# Kilobot_Controller_Hub_FTDI.net
KiCad netlist of a schematic drawn in Altium Designer
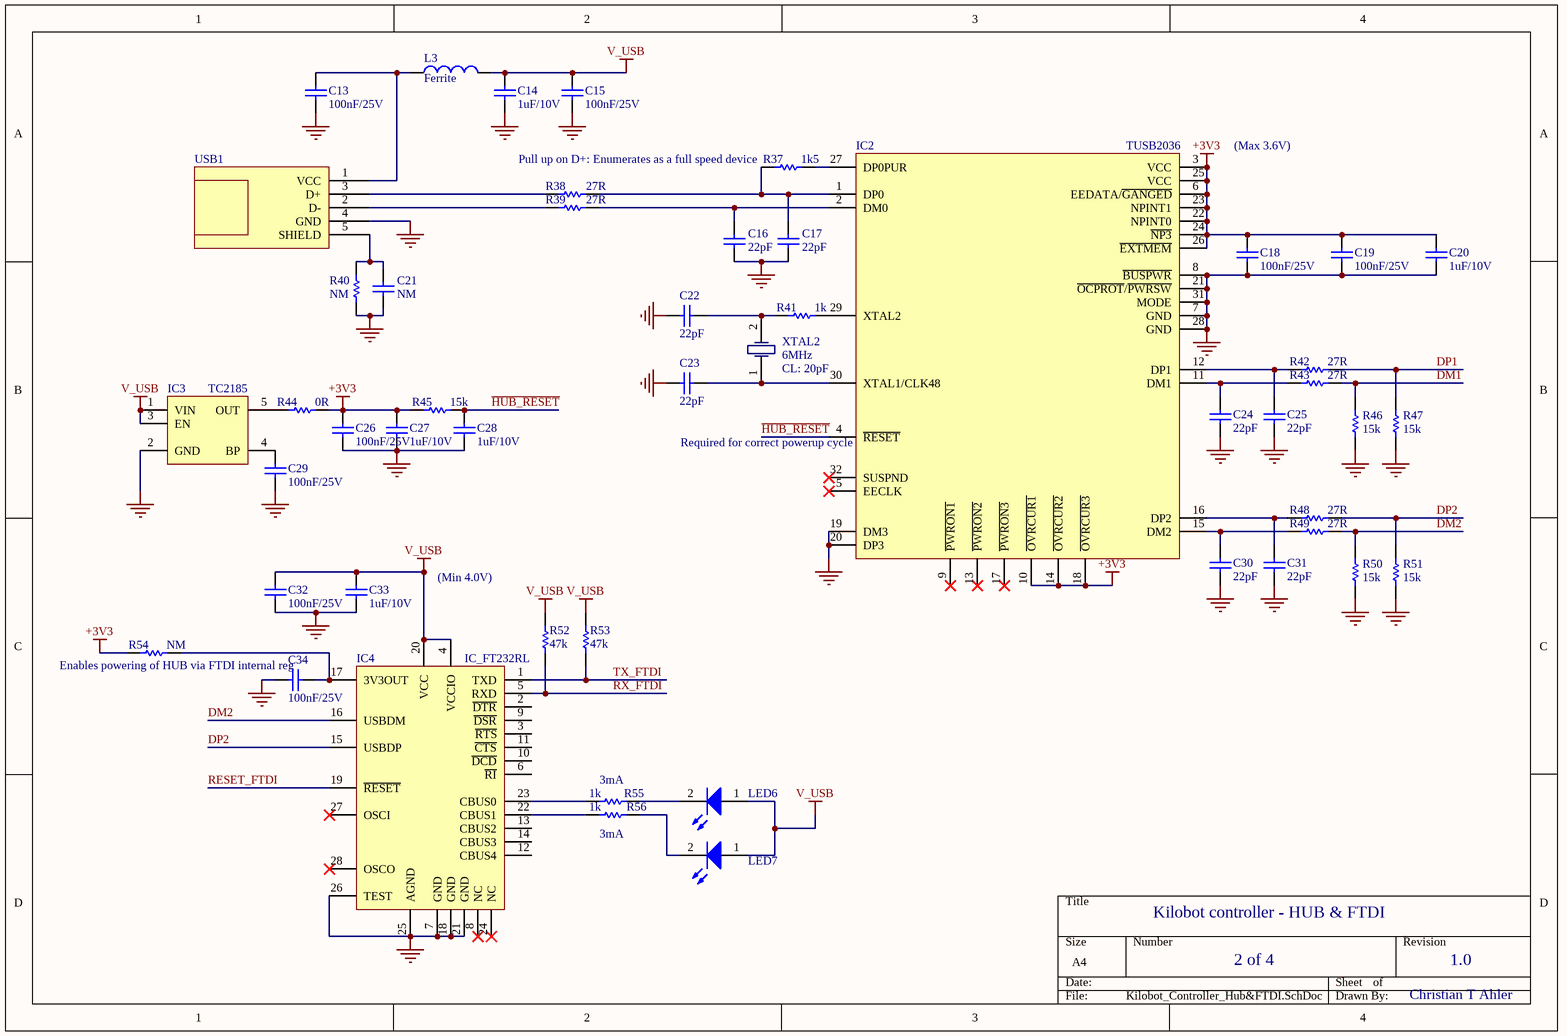
[diagram p0: Kilobot_Controller_Hub&FTDI.SchDoc]

(export (version "E")
  (design (tool "Eeschema 10.0.6"))
  (components
    (comp (ref "C13")
      (value "100nF/25V")
      (footprint "RESC1608L")
      (description "Ceramic Chip Capacitor - Standard")
      (fields (field (name "Comment") "C0603"))
      (libsource (lib "KEMET Chip Capacitor") (part "C0603"))
    )
    (comp (ref "C14")
      (value "1uF/10V")
      (footprint "RESC1608L")
      (description "Ceramic Chip Capacitor - Standard")
      (fields (field (name "Comment") "C0603"))
      (libsource (lib "KEMET Chip Capacitor") (part "C0603"))
    )
    (comp (ref "C15")
      (value "100nF/25V")
      (footprint "RESC1608L")
      (description "Ceramic Chip Capacitor - Standard")
      (fields (field (name "Comment") "C0603"))
      (libsource (lib "KEMET Chip Capacitor") (part "C0603"))
    )
    (comp (ref "C16")
      (value "22pF")
      (footprint "RESC1608L")
      (description "Ceramic Chip Capacitor - Standard")
      (fields (field (name "Comment") "C0603"))
      (libsource (lib "KEMET Chip Capacitor") (part "C0603"))
    )
    (comp (ref "C17")
      (value "22pF")
      (footprint "RESC1608L")
      (description "Ceramic Chip Capacitor - Standard")
      (fields (field (name "Comment") "C0603"))
      (libsource (lib "KEMET Chip Capacitor") (part "C0603"))
    )
    (comp (ref "C18")
      (value "100nF/25V")
      (footprint "RESC1608L")
      (description "Ceramic Chip Capacitor - Standard")
      (fields (field (name "Comment") "C0603"))
      (libsource (lib "KEMET Chip Capacitor") (part "C0603"))
    )
    (comp (ref "C19")
      (value "100nF/25V")
      (footprint "RESC1608L")
      (description "Ceramic Chip Capacitor - Standard")
      (fields (field (name "Comment") "C0603"))
      (libsource (lib "KEMET Chip Capacitor") (part "C0603"))
    )
    (comp (ref "C20")
      (value "1uF/10V")
      (footprint "RESC1608L")
      (description "Ceramic Chip Capacitor - Standard")
      (fields (field (name "Comment") "C0603"))
      (libsource (lib "KEMET Chip Capacitor") (part "C0603"))
    )
    (comp (ref "C21")
      (value "NM")
      (footprint "RESC1608L")
      (description "Ceramic Chip Capacitor - Standard")
      (fields (field (name "Comment") "C0603"))
      (libsource (lib "KEMET Chip Capacitor") (part "C0603"))
    )
    (comp (ref "C22")
      (value "22pF")
      (footprint "RESC1608L")
      (description "Ceramic Chip Capacitor - Standard")
      (fields (field (name "Comment") "C0603"))
      (libsource (lib "KEMET Chip Capacitor") (part "C0603"))
    )
    (comp (ref "C23")
      (value "22pF")
      (footprint "RESC1608L")
      (description "Ceramic Chip Capacitor - Standard")
      (fields (field (name "Comment") "C0603"))
      (libsource (lib "KEMET Chip Capacitor") (part "C0603"))
    )
    (comp (ref "C24")
      (value "22pF")
      (footprint "RESC1608L")
      (description "Ceramic Chip Capacitor - Standard")
      (fields (field (name "Comment") "C0603"))
      (libsource (lib "KEMET Chip Capacitor") (part "C0603"))
    )
    (comp (ref "C25")
      (value "22pF")
      (footprint "RESC1608L")
      (description "Ceramic Chip Capacitor - Standard")
      (fields (field (name "Comment") "C0603"))
      (libsource (lib "KEMET Chip Capacitor") (part "C0603"))
    )
    (comp (ref "C26")
      (value "100nF/25V")
      (footprint "RESC1608L")
      (description "Ceramic Chip Capacitor - Standard")
      (fields (field (name "Comment") "C0603"))
      (libsource (lib "KEMET Chip Capacitor") (part "C0603"))
    )
    (comp (ref "C27")
      (value "1uF/10V")
      (footprint "RESC1608L")
      (description "Ceramic Chip Capacitor - Standard")
      (fields (field (name "Comment") "C0603"))
      (libsource (lib "KEMET Chip Capacitor") (part "C0603"))
    )
    (comp (ref "C28")
      (value "1uF/10V")
      (footprint "RESC1608L")
      (description "Ceramic Chip Capacitor - Standard")
      (fields (field (name "Comment") "C0603"))
      (libsource (lib "KEMET Chip Capacitor") (part "C0603"))
    )
    (comp (ref "C29")
      (value "100nF/25V")
      (footprint "RESC1608L")
      (description "Ceramic Chip Capacitor - Standard")
      (fields (field (name "Comment") "C0603"))
      (libsource (lib "KEMET Chip Capacitor") (part "C0603"))
    )
    (comp (ref "C30")
      (value "22pF")
      (footprint "RESC1608L")
      (description "Ceramic Chip Capacitor - Standard")
      (fields (field (name "Comment") "C0603"))
      (libsource (lib "KEMET Chip Capacitor") (part "C0603"))
    )
    (comp (ref "C31")
      (value "22pF")
      (footprint "RESC1608L")
      (description "Ceramic Chip Capacitor - Standard")
      (fields (field (name "Comment") "C0603"))
      (libsource (lib "KEMET Chip Capacitor") (part "C0603"))
    )
    (comp (ref "C32")
      (value "100nF/25V")
      (footprint "RESC1608L")
      (description "Ceramic Chip Capacitor - Standard")
      (fields (field (name "Comment") "C0603"))
      (libsource (lib "KEMET Chip Capacitor") (part "C0603"))
    )
    (comp (ref "C33")
      (value "1uF/10V")
      (footprint "RESC1608L")
      (description "Ceramic Chip Capacitor - Standard")
      (fields (field (name "Comment") "C0603"))
      (libsource (lib "KEMET Chip Capacitor") (part "C0603"))
    )
    (comp (ref "C34")
      (value "100nF/25V")
      (footprint "RESC1608L")
      (description "Ceramic Chip Capacitor - Standard")
      (fields (field (name "Comment") "C0603"))
      (libsource (lib "KEMET Chip Capacitor") (part "C0603"))
    )
    (comp (ref "IC2")
      (value "TUSB2036")
      (footprint "TQFP32")
      (libsource (lib "Kilobot_Controller") (part "TUSB2036"))
    )
    (comp (ref "IC3")
      (value "TC2185")
      (footprint "SOT23-5")
      (libsource (lib "Kilobot_Controller") (part "TC2185"))
    )
    (comp (ref "IC4")
      (value "IC_FT232RL")
      (footprint "SSOP-28")
      (description "FT232R USB UART")
      (libsource (lib "FTDI_SCH_Public") (part "IC_FT232RL"))
    )
    (comp (ref "L3")
      (value "Ferrite")
      (footprint "RESC2012N")
      (description "Inductor")
      (libsource (lib "Miscellaneous Devices") (part "Inductor"))
    )
    (comp (ref "LED6") (value "LED") (footprint "LED0603") (libsource (lib "KilobotCommercial") (part "LED")))
    (comp (ref "LED7") (value "LED") (footprint "LED0603") (libsource (lib "KilobotCommercial") (part "LED")))
    (comp (ref "R37")
      (value "1k5")
      (footprint "RESC1608L")
      (description "Resistor")
      (fields (field (name "Comment") "Res1"))
      (libsource (lib "Miscellaneous Devices") (part "Res1"))
    )
    (comp (ref "R38")
      (value "27R")
      (footprint "RESC1608L")
      (description "Resistor")
      (fields (field (name "Comment") "Res1"))
      (libsource (lib "Miscellaneous Devices") (part "Res1"))
    )
    (comp (ref "R39")
      (value "27R")
      (footprint "RESC1608L")
      (description "Resistor")
      (fields (field (name "Comment") "Res1"))
      (libsource (lib "Miscellaneous Devices") (part "Res1"))
    )
    (comp (ref "R40")
      (value "NM")
      (footprint "RESC1608L")
      (description "Resistor")
      (fields (field (name "Comment") "Res1"))
      (libsource (lib "Miscellaneous Devices") (part "Res1"))
    )
    (comp (ref "R41")
      (value "1k")
      (footprint "RESC1608L")
      (description "Resistor")
      (fields (field (name "Comment") "Res1"))
      (libsource (lib "Miscellaneous Devices") (part "Res1"))
    )
    (comp (ref "R42")
      (value "27R")
      (footprint "RESC1608L")
      (description "Resistor")
      (fields (field (name "Comment") "Res1"))
      (libsource (lib "Miscellaneous Devices") (part "Res1"))
    )
    (comp (ref "R43")
      (value "27R")
      (footprint "RESC1608L")
      (description "Resistor")
      (fields (field (name "Comment") "Res1"))
      (libsource (lib "Miscellaneous Devices") (part "Res1"))
    )
    (comp (ref "R44")
      (value "0R")
      (footprint "RESC1608L")
      (description "Resistor")
      (fields (field (name "Comment") "Res1"))
      (libsource (lib "Miscellaneous Devices") (part "Res1"))
    )
    (comp (ref "R45")
      (value "15k")
      (footprint "RESC1608L")
      (description "Resistor")
      (fields (field (name "Comment") "Res1"))
      (libsource (lib "Miscellaneous Devices") (part "Res1"))
    )
    (comp (ref "R46")
      (value "15k")
      (footprint "RESC1608L")
      (description "Resistor")
      (fields (field (name "Comment") "Res1"))
      (libsource (lib "Miscellaneous Devices") (part "Res1"))
    )
    (comp (ref "R47")
      (value "15k")
      (footprint "RESC1608L")
      (description "Resistor")
      (fields (field (name "Comment") "Res1"))
      (libsource (lib "Miscellaneous Devices") (part "Res1"))
    )
    (comp (ref "R48")
      (value "27R")
      (footprint "RESC1608L")
      (description "Resistor")
      (fields (field (name "Comment") "Res1"))
      (libsource (lib "Miscellaneous Devices") (part "Res1"))
    )
    (comp (ref "R49")
      (value "27R")
      (footprint "RESC1608L")
      (description "Resistor")
      (fields (field (name "Comment") "Res1"))
      (libsource (lib "Miscellaneous Devices") (part "Res1"))
    )
    (comp (ref "R50")
      (value "15k")
      (footprint "RESC1608L")
      (description "Resistor")
      (fields (field (name "Comment") "Res1"))
      (libsource (lib "Miscellaneous Devices") (part "Res1"))
    )
    (comp (ref "R51")
      (value "15k")
      (footprint "RESC1608L")
      (description "Resistor")
      (fields (field (name "Comment") "Res1"))
      (libsource (lib "Miscellaneous Devices") (part "Res1"))
    )
    (comp (ref "R52")
      (value "47k")
      (footprint "RESC1608L")
      (description "Resistor")
      (fields (field (name "Comment") "Res1"))
      (libsource (lib "Miscellaneous Devices") (part "Res1"))
    )
    (comp (ref "R53")
      (value "47k")
      (footprint "RESC1608L")
      (description "Resistor")
      (fields (field (name "Comment") "Res1"))
      (libsource (lib "Miscellaneous Devices") (part "Res1"))
    )
    (comp (ref "R54")
      (value "NM")
      (footprint "RESC1608L")
      (description "Resistor")
      (fields (field (name "Comment") "Res1"))
      (libsource (lib "Miscellaneous Devices") (part "Res1"))
    )
    (comp (ref "R55")
      (value "1k")
      (footprint "RESC1608L")
      (description "Resistor")
      (fields (field (name "Comment") "Res1"))
      (libsource (lib "Miscellaneous Devices") (part "Res1"))
    )
    (comp (ref "R56")
      (value "1k")
      (footprint "RESC1608L")
      (description "Resistor")
      (fields (field (name "Comment") "Res1"))
      (libsource (lib "Miscellaneous Devices") (part "Res1"))
    )
    (comp (ref "USB1")
      (value "USB")
      (footprint "USB_Vertical")
      (libsource (lib "Kilobot_Controller") (part "USB"))
    )
    (comp (ref "XTAL2")
      (value "6MHz")
      (footprint "CrystalSMD")
      (fields (field (name "CL") "20pF") (field (name "Comment") "CrystalSMD"))
      (libsource (lib "Kilobot_Controller") (part "CrystalSMD"))
    )
  )
  (nets
    (net (code "1") (name "+3V3") (class "Default")
      (node (ref "C18") (pin "2") (pinfunction "2_2") (pintype "passive"))
      (node (ref "C19") (pin "2") (pinfunction "2_2") (pintype "passive"))
      (node (ref "C20") (pin "2") (pinfunction "2_2") (pintype "passive"))
      (node (ref "C26") (pin "2") (pinfunction "2_2") (pintype "passive"))
      (node (ref "C27") (pin "2") (pinfunction "2_2") (pintype "passive"))
      (node (ref "IC2") (pin "10") (pinfunction "~{OVRCUR1}_10") (pintype "passive"))
      (node (ref "IC2") (pin "14") (pinfunction "~{OVRCUR2}_14") (pintype "passive"))
      (node (ref "IC2") (pin "18") (pinfunction "~{OVRCUR3}_18") (pintype "passive"))
      (node (ref "IC2") (pin "22") (pinfunction "NPINT0_22") (pintype "passive"))
      (node (ref "IC2") (pin "23") (pinfunction "NPINT1_23") (pintype "passive"))
      (node (ref "IC2") (pin "24") (pinfunction "~{NP3}_24") (pintype "passive"))
      (node (ref "IC2") (pin "25") (pinfunction "VCC_25") (pintype "passive"))
      (node (ref "IC2") (pin "26") (pinfunction "~{EXTMEM}_26") (pintype "passive"))
      (node (ref "IC2") (pin "3") (pinfunction "VCC_3") (pintype "passive"))
      (node (ref "IC2") (pin "6") (pinfunction "EEDATA/~{GANGED}_6") (pintype "passive"))
      (node (ref "R44") (pin "1") (pinfunction "1_1") (pintype "passive"))
      (node (ref "R45") (pin "2") (pinfunction "2_2") (pintype "passive"))
      (node (ref "R54") (pin "2") (pinfunction "2_2") (pintype "passive"))
    )
    (net (code "2") (name "/DM1") (class "Default")
      (node (ref "R43") (pin "1") (pinfunction "1_1") (pintype "passive"))
      (node (ref "R46") (pin "1") (pinfunction "1_1") (pintype "passive"))
    )
    (net (code "3") (name "/DM2") (class "Default")
      (node (ref "IC4") (pin "16") (pinfunction "USBDM_16") (pintype "passive"))
      (node (ref "R49") (pin "1") (pinfunction "1_1") (pintype "passive"))
      (node (ref "R50") (pin "1") (pinfunction "1_1") (pintype "passive"))
    )
    (net (code "4") (name "/DP1") (class "Default")
      (node (ref "R42") (pin "1") (pinfunction "1_1") (pintype "passive"))
      (node (ref "R47") (pin "1") (pinfunction "1_1") (pintype "passive"))
    )
    (net (code "5") (name "/DP2") (class "Default")
      (node (ref "IC4") (pin "15") (pinfunction "USBDP_15") (pintype "passive"))
      (node (ref "R48") (pin "1") (pinfunction "1_1") (pintype "passive"))
      (node (ref "R51") (pin "1") (pinfunction "1_1") (pintype "passive"))
    )
    (net (code "6") (name "/RESET_FTDI") (class "Default")
      (node (ref "IC4") (pin "19") (pinfunction "~{RESET}_19") (pintype "passive"))
    )
    (net (code "7") (name "/RX_FTDI") (class "Default")
      (node (ref "IC4") (pin "5") (pinfunction "RXD_5") (pintype "passive"))
      (node (ref "R52") (pin "1") (pinfunction "1_1") (pintype "passive"))
    )
    (net (code "8") (name "/TX_FTDI") (class "Default")
      (node (ref "IC4") (pin "1") (pinfunction "TXD_1") (pintype "passive"))
      (node (ref "R53") (pin "1") (pinfunction "1_1") (pintype "passive"))
    )
    (net (code "9") (name "/~{HUB_RESET}") (class "Default")
      (node (ref "C28") (pin "2") (pinfunction "2_2") (pintype "passive"))
      (node (ref "IC2") (pin "4") (pinfunction "~{RESET}_4") (pintype "passive"))
      (node (ref "R45") (pin "1") (pinfunction "1_1") (pintype "passive"))
    )
    (net (code "10") (name "GND") (class "Default")
      (node (ref "C13") (pin "1") (pinfunction "1_1") (pintype "passive"))
      (node (ref "C14") (pin "2") (pinfunction "2_2") (pintype "passive"))
      (node (ref "C15") (pin "1") (pinfunction "1_1") (pintype "passive"))
      (node (ref "C16") (pin "1") (pinfunction "1_1") (pintype "passive"))
      (node (ref "C17") (pin "1") (pinfunction "1_1") (pintype "passive"))
      (node (ref "C18") (pin "1") (pinfunction "1_1") (pintype "passive"))
      (node (ref "C19") (pin "1") (pinfunction "1_1") (pintype "passive"))
      (node (ref "C20") (pin "1") (pinfunction "1_1") (pintype "passive"))
      (node (ref "C21") (pin "2") (pinfunction "2_2") (pintype "passive"))
      (node (ref "C22") (pin "1") (pinfunction "1_1") (pintype "passive"))
      (node (ref "C23") (pin "1") (pinfunction "1_1") (pintype "passive"))
      (node (ref "C24") (pin "1") (pinfunction "1_1") (pintype "passive"))
      (node (ref "C25") (pin "1") (pinfunction "1_1") (pintype "passive"))
      (node (ref "C26") (pin "1") (pinfunction "1_1") (pintype "passive"))
      (node (ref "C27") (pin "1") (pinfunction "1_1") (pintype "passive"))
      (node (ref "C28") (pin "1") (pinfunction "1_1") (pintype "passive"))
      (node (ref "C29") (pin "2") (pinfunction "2_2") (pintype "passive"))
      (node (ref "C30") (pin "1") (pinfunction "1_1") (pintype "passive"))
      (node (ref "C31") (pin "1") (pinfunction "1_1") (pintype "passive"))
      (node (ref "C32") (pin "2") (pinfunction "2_2") (pintype "passive"))
      (node (ref "C33") (pin "1") (pinfunction "1_1") (pintype "passive"))
      (node (ref "C34") (pin "2") (pinfunction "2_2") (pintype "passive"))
      (node (ref "IC2") (pin "19") (pinfunction "DM3_19") (pintype "passive"))
      (node (ref "IC2") (pin "20") (pinfunction "DP3_20") (pintype "passive"))
      (node (ref "IC2") (pin "21") (pinfunction "~{OCPROT}/~{PWRSW}_21") (pintype "passive"))
      (node (ref "IC2") (pin "28") (pinfunction "GND_28") (pintype "passive"))
      (node (ref "IC2") (pin "31") (pinfunction "MODE_31") (pintype "passive"))
      (node (ref "IC2") (pin "7") (pinfunction "GND_7") (pintype "passive"))
      (node (ref "IC2") (pin "8") (pinfunction "~{BUSPWR}_8") (pintype "passive"))
      (node (ref "IC3") (pin "2") (pinfunction "GND_2") (pintype "passive"))
      (node (ref "IC4") (pin "18") (pinfunction "GND_18") (pintype "passive"))
      (node (ref "IC4") (pin "21") (pinfunction "GND_21") (pintype "passive"))
      (node (ref "IC4") (pin "25") (pinfunction "AGND_25") (pintype "passive"))
      (node (ref "IC4") (pin "26") (pinfunction "TEST_26") (pintype "passive"))
      (node (ref "IC4") (pin "7") (pinfunction "GND_7") (pintype "passive"))
      (node (ref "R40") (pin "2") (pinfunction "2_2") (pintype "passive"))
      (node (ref "R46") (pin "2") (pinfunction "2_2") (pintype "passive"))
      (node (ref "R47") (pin "2") (pinfunction "2_2") (pintype "passive"))
      (node (ref "R50") (pin "2") (pinfunction "2_2") (pintype "passive"))
      (node (ref "R51") (pin "2") (pinfunction "2_2") (pintype "passive"))
      (node (ref "USB1") (pin "4") (pinfunction "GND_4") (pintype "passive"))
    )
    (net (code "11") (name "Net-(C22-Pad2)") (class "Default")
      (node (ref "C22") (pin "2") (pinfunction "2_2") (pintype "passive"))
      (node (ref "R41") (pin "2") (pinfunction "2_2") (pintype "passive"))
      (node (ref "XTAL2") (pin "2") (pinfunction "2_2") (pintype "passive"))
    )
    (net (code "12") (name "Net-(IC2-DM0)") (class "Default")
      (node (ref "C16") (pin "2") (pinfunction "2_2") (pintype "passive"))
      (node (ref "IC2") (pin "2") (pinfunction "DM0_2") (pintype "passive"))
      (node (ref "R39") (pin "1") (pinfunction "1_1") (pintype "passive"))
    )
    (net (code "13") (name "Net-(IC2-DM1)") (class "Default")
      (node (ref "C24") (pin "2") (pinfunction "2_2") (pintype "passive"))
      (node (ref "IC2") (pin "11") (pinfunction "DM1_11") (pintype "passive"))
      (node (ref "R43") (pin "2") (pinfunction "2_2") (pintype "passive"))
    )
    (net (code "14") (name "Net-(IC2-DM2)") (class "Default")
      (node (ref "C30") (pin "2") (pinfunction "2_2") (pintype "passive"))
      (node (ref "IC2") (pin "15") (pinfunction "DM2_15") (pintype "passive"))
      (node (ref "R49") (pin "2") (pinfunction "2_2") (pintype "passive"))
    )
    (net (code "15") (name "Net-(IC2-DP0)") (class "Default")
      (node (ref "C17") (pin "2") (pinfunction "2_2") (pintype "passive"))
      (node (ref "IC2") (pin "1") (pinfunction "DP0_1") (pintype "passive"))
      (node (ref "R37") (pin "2") (pinfunction "2_2") (pintype "passive"))
      (node (ref "R38") (pin "1") (pinfunction "1_1") (pintype "passive"))
    )
    (net (code "16") (name "Net-(IC2-DP0PUR)") (class "Default")
      (node (ref "IC2") (pin "27") (pinfunction "DP0PUR_27") (pintype "passive"))
      (node (ref "R37") (pin "1") (pinfunction "1_1") (pintype "passive"))
    )
    (net (code "17") (name "Net-(IC2-DP1)") (class "Default")
      (node (ref "C25") (pin "2") (pinfunction "2_2") (pintype "passive"))
      (node (ref "IC2") (pin "12") (pinfunction "DP1_12") (pintype "passive"))
      (node (ref "R42") (pin "2") (pinfunction "2_2") (pintype "passive"))
    )
    (net (code "18") (name "Net-(IC2-DP2)") (class "Default")
      (node (ref "C31") (pin "2") (pinfunction "2_2") (pintype "passive"))
      (node (ref "IC2") (pin "16") (pinfunction "DP2_16") (pintype "passive"))
      (node (ref "R48") (pin "2") (pinfunction "2_2") (pintype "passive"))
    )
    (net (code "19") (name "Net-(IC2-XTAL1{slash}CLK48)") (class "Default")
      (node (ref "C23") (pin "2") (pinfunction "2_2") (pintype "passive"))
      (node (ref "IC2") (pin "30") (pinfunction "XTAL1/CLK48_30") (pintype "passive"))
      (node (ref "XTAL2") (pin "1") (pinfunction "1_1") (pintype "passive"))
    )
    (net (code "20") (name "Net-(IC2-XTAL2)") (class "Default")
      (node (ref "IC2") (pin "29") (pinfunction "XTAL2_29") (pintype "passive"))
      (node (ref "R41") (pin "1") (pinfunction "1_1") (pintype "passive"))
    )
    (net (code "21") (name "Net-(IC3-BP)") (class "Default")
      (node (ref "C29") (pin "1") (pinfunction "1_1") (pintype "passive"))
      (node (ref "IC3") (pin "4") (pinfunction "BP_4") (pintype "passive"))
    )
    (net (code "22") (name "Net-(IC3-OUT)") (class "Default")
      (node (ref "IC3") (pin "5") (pinfunction "OUT_5") (pintype "passive"))
      (node (ref "R44") (pin "2") (pinfunction "2_2") (pintype "passive"))
    )
    (net (code "23") (name "Net-(IC4-3V3OUT)") (class "Default")
      (node (ref "C34") (pin "1") (pinfunction "1_1") (pintype "passive"))
      (node (ref "IC4") (pin "17") (pinfunction "3V3OUT_17") (pintype "passive"))
      (node (ref "R54") (pin "1") (pinfunction "1_1") (pintype "passive"))
    )
    (net (code "24") (name "Net-(IC4-CBUS0)") (class "Default")
      (node (ref "IC4") (pin "23") (pinfunction "CBUS0_23") (pintype "passive"))
      (node (ref "R55") (pin "1") (pinfunction "1_1") (pintype "passive"))
    )
    (net (code "25") (name "Net-(IC4-CBUS1)") (class "Default")
      (node (ref "IC4") (pin "22") (pinfunction "CBUS1_22") (pintype "passive"))
      (node (ref "R56") (pin "1") (pinfunction "1_1") (pintype "passive"))
    )
    (net (code "26") (name "Net-(LED6-K)") (class "Default")
      (node (ref "LED6") (pin "2") (pinfunction "K_2") (pintype "passive"))
      (node (ref "R55") (pin "2") (pinfunction "2_2") (pintype "passive"))
    )
    (net (code "27") (name "Net-(LED7-K)") (class "Default")
      (node (ref "LED7") (pin "2") (pinfunction "K_2") (pintype "passive"))
      (node (ref "R56") (pin "2") (pinfunction "2_2") (pintype "passive"))
    )
    (net (code "28") (name "Net-(USB1-D+)") (class "Default")
      (node (ref "R38") (pin "2") (pinfunction "2_2") (pintype "passive"))
      (node (ref "USB1") (pin "3") (pinfunction "D+_3") (pintype "passive"))
    )
    (net (code "29") (name "Net-(USB1-D-)") (class "Default")
      (node (ref "R39") (pin "2") (pinfunction "2_2") (pintype "passive"))
      (node (ref "USB1") (pin "2") (pinfunction "D-_2") (pintype "passive"))
    )
    (net (code "30") (name "Net-(USB1-SHIELD)") (class "Default")
      (node (ref "C21") (pin "1") (pinfunction "1_1") (pintype "passive"))
      (node (ref "R40") (pin "1") (pinfunction "1_1") (pintype "passive"))
      (node (ref "USB1") (pin "5") (pinfunction "SHIELD_5") (pintype "passive"))
    )
    (net (code "31") (name "Net-(USB1-VCC)") (class "Default")
      (node (ref "C13") (pin "2") (pinfunction "2_2") (pintype "passive"))
      (node (ref "L3") (pin "1") (pinfunction "1_1") (pintype "passive"))
      (node (ref "USB1") (pin "1") (pinfunction "VCC_1") (pintype "passive"))
    )
    (net (code "32") (name "V_USB") (class "Default")
      (node (ref "C14") (pin "1") (pinfunction "1_1") (pintype "passive"))
      (node (ref "C15") (pin "2") (pinfunction "2_2") (pintype "passive"))
      (node (ref "C32") (pin "1") (pinfunction "1_1") (pintype "passive"))
      (node (ref "C33") (pin "2") (pinfunction "2_2") (pintype "passive"))
      (node (ref "IC3") (pin "1") (pinfunction "VIN_1") (pintype "passive"))
      (node (ref "IC3") (pin "3") (pinfunction "EN_3") (pintype "passive"))
      (node (ref "IC4") (pin "20") (pinfunction "VCC_20") (pintype "passive"))
      (node (ref "IC4") (pin "4") (pinfunction "VCCIO_4") (pintype "passive"))
      (node (ref "L3") (pin "2") (pinfunction "2_2") (pintype "passive"))
      (node (ref "LED6") (pin "1") (pinfunction "A_1") (pintype "passive"))
      (node (ref "LED7") (pin "1") (pinfunction "A_1") (pintype "passive"))
      (node (ref "R52") (pin "2") (pinfunction "2_2") (pintype "passive"))
      (node (ref "R53") (pin "2") (pinfunction "2_2") (pintype "passive"))
    )
    (net (code "33") (name "unconnected-(IC2-EECLK-Pad5)") (class "Default")
      (node (ref "IC2") (pin "5") (pinfunction "EECLK_5") (pintype "passive+no_connect"))
    )
    (net (code "34") (name "unconnected-(IC2-SUSPND-Pad32)") (class "Default")
      (node (ref "IC2") (pin "32") (pinfunction "SUSPND_32") (pintype "passive+no_connect"))
    )
    (net (code "35") (name "unconnected-(IC2-~{PWRON1}-Pad9)") (class "Default")
      (node (ref "IC2") (pin "9") (pinfunction "~{PWRON1}_9") (pintype "passive+no_connect"))
    )
    (net (code "36") (name "unconnected-(IC2-~{PWRON2}-Pad13)") (class "Default")
      (node (ref "IC2") (pin "13") (pinfunction "~{PWRON2}_13") (pintype "passive+no_connect"))
    )
    (net (code "37") (name "unconnected-(IC2-~{PWRON3}-Pad17)") (class "Default")
      (node (ref "IC2") (pin "17") (pinfunction "~{PWRON3}_17") (pintype "passive+no_connect"))
    )
    (net (code "38") (name "unconnected-(IC4-CBUS2-Pad13)") (class "Default")
      (node (ref "IC4") (pin "13") (pinfunction "CBUS2_13") (pintype "passive"))
    )
    (net (code "39") (name "unconnected-(IC4-CBUS3-Pad14)") (class "Default")
      (node (ref "IC4") (pin "14") (pinfunction "CBUS3_14") (pintype "passive"))
    )
    (net (code "40") (name "unconnected-(IC4-CBUS4-Pad12)") (class "Default")
      (node (ref "IC4") (pin "12") (pinfunction "CBUS4_12") (pintype "passive"))
    )
    (net (code "41") (name "unconnected-(IC4-NC-Pad8)") (class "Default")
      (node (ref "IC4") (pin "8") (pinfunction "NC_8") (pintype "passive+no_connect"))
    )
    (net (code "42") (name "unconnected-(IC4-NC-Pad24)") (class "Default")
      (node (ref "IC4") (pin "24") (pinfunction "NC_24") (pintype "passive+no_connect"))
    )
    (net (code "43") (name "unconnected-(IC4-OSCI-Pad27)") (class "Default")
      (node (ref "IC4") (pin "27") (pinfunction "OSCI_27") (pintype "passive+no_connect"))
    )
    (net (code "44") (name "unconnected-(IC4-OSCO-Pad28)") (class "Default")
      (node (ref "IC4") (pin "28") (pinfunction "OSCO_28") (pintype "passive+no_connect"))
    )
    (net (code "45") (name "unconnected-(IC4-~{CTS}-Pad11)") (class "Default")
      (node (ref "IC4") (pin "11") (pinfunction "~{CTS}_11") (pintype "passive"))
    )
    (net (code "46") (name "unconnected-(IC4-~{DCD}-Pad10)") (class "Default")
      (node (ref "IC4") (pin "10") (pinfunction "~{DCD}_10") (pintype "passive"))
    )
    (net (code "47") (name "unconnected-(IC4-~{DSR}-Pad9)") (class "Default")
      (node (ref "IC4") (pin "9") (pinfunction "~{DSR}_9") (pintype "passive"))
    )
    (net (code "48") (name "unconnected-(IC4-~{DTR}-Pad2)") (class "Default")
      (node (ref "IC4") (pin "2") (pinfunction "~{DTR}_2") (pintype "passive"))
    )
    (net (code "49") (name "unconnected-(IC4-~{RI}-Pad6)") (class "Default")
      (node (ref "IC4") (pin "6") (pinfunction "~{RI}_6") (pintype "passive"))
    )
    (net (code "50") (name "unconnected-(IC4-~{RTS}-Pad3)") (class "Default")
      (node (ref "IC4") (pin "3") (pinfunction "~{RTS}_3") (pintype "passive"))
    )
  )
)
